# PiezoPreamp.net
KiCad netlist of a schematic drawn in EAGLE
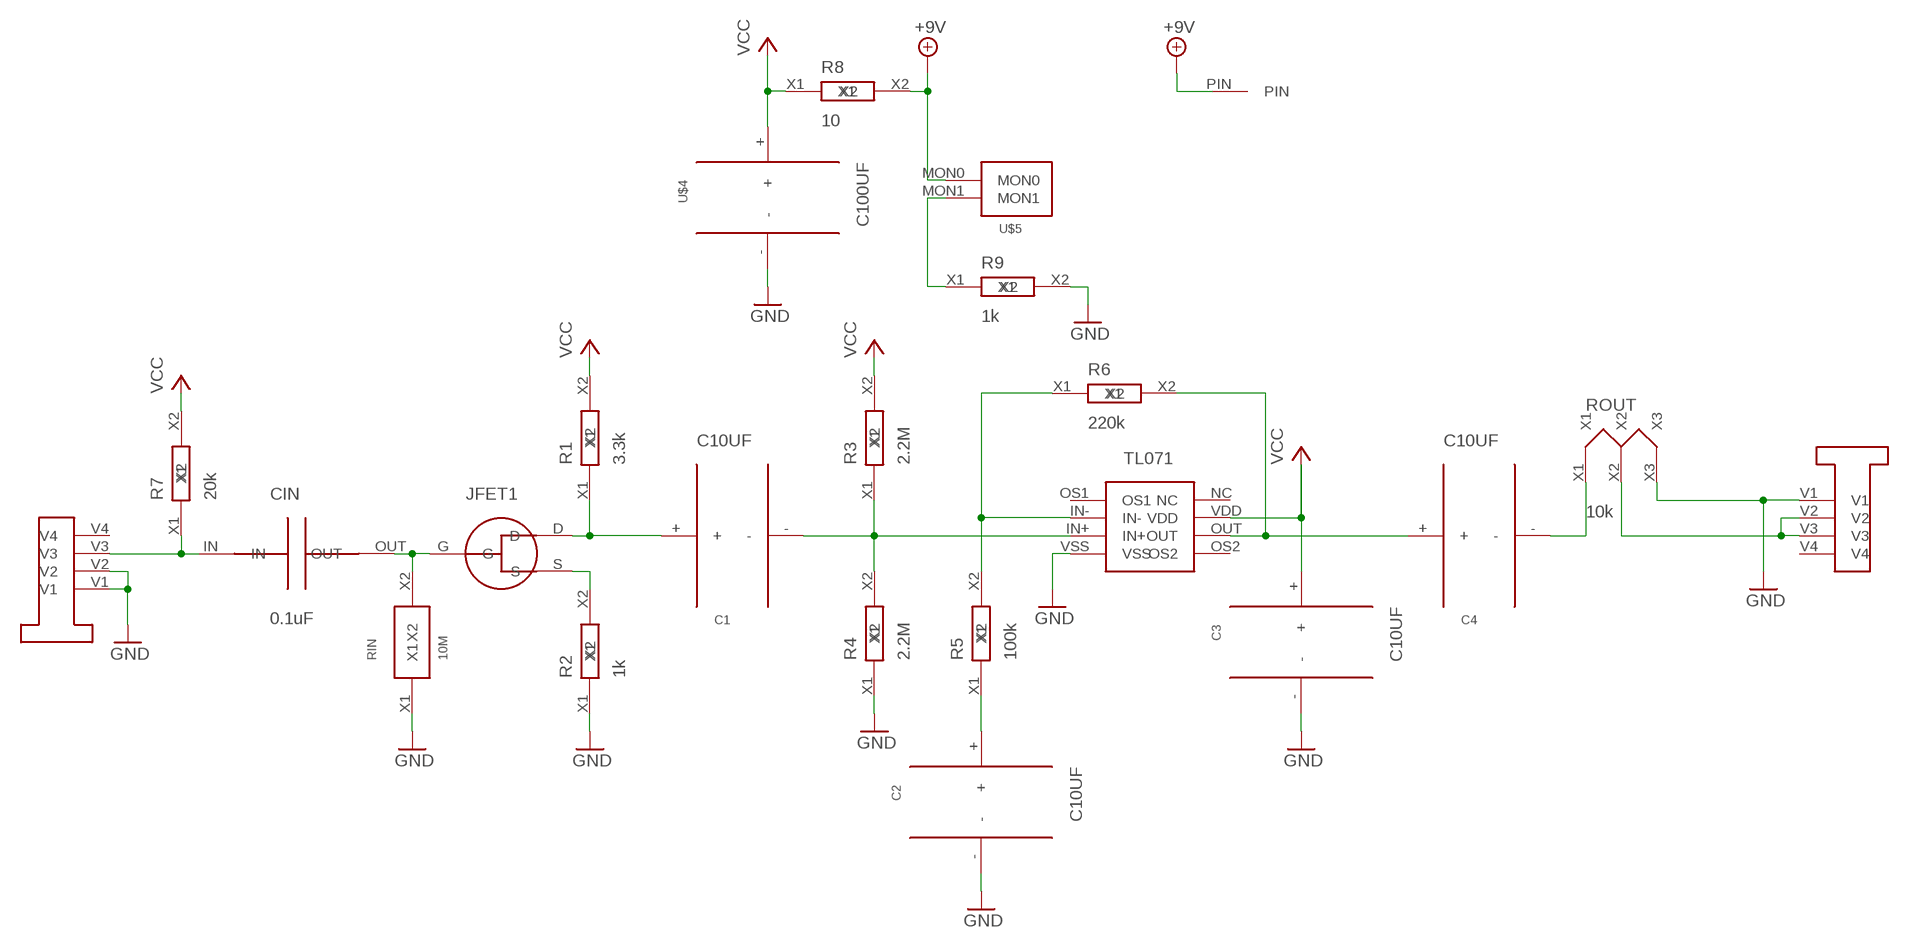
[diagram p0: schematic, sheet 1]

(export (version "E")
  (design (tool "Eeschema 10.0.6"))
  (components
    (comp (ref "C1")
      (value "C10UF")
      (footprint "eagle-import:C10UF")
      (libsource (lib "eagle-import") (part "C10UF"))
    )
    (comp (ref "C2")
      (value "C10UF")
      (footprint "eagle-import:C10UF")
      (libsource (lib "eagle-import") (part "C10UF"))
    )
    (comp (ref "C3")
      (value "C10UF")
      (footprint "eagle-import:C10UF")
      (libsource (lib "eagle-import") (part "C10UF"))
    )
    (comp (ref "C4")
      (value "C10UF")
      (footprint "eagle-import:C10UF")
      (libsource (lib "eagle-import") (part "C10UF"))
    )
    (comp (ref "CIN")
      (value "0.1uF")
      (footprint "eagle-import:C_CER_5MM")
      (libsource (lib "eagle-import") (part "C_CER_5MM"))
    )
    (comp (ref "JFET1")
      (value "2N5457_H")
      (footprint "eagle-import:2N5457_H")
      (libsource (lib "eagle-import") (part "2N5457_H"))
    )
    (comp (ref "R1")
      (value "3.3k")
      (footprint "eagle-import:SMD_2.1X1.25")
      (libsource (lib "eagle-import") (part "R_SMD_2.1X1.25"))
    )
    (comp (ref "R2")
      (value "1k")
      (footprint "eagle-import:SMD_2.1X1.25")
      (libsource (lib "eagle-import") (part "R_SMD_2.1X1.25"))
    )
    (comp (ref "R3")
      (value "2.2M")
      (footprint "eagle-import:SMD_2.1X1.25")
      (libsource (lib "eagle-import") (part "R_SMD_2.1X1.25"))
    )
    (comp (ref "R4")
      (value "2.2M")
      (footprint "eagle-import:SMD_2.1X1.25")
      (libsource (lib "eagle-import") (part "R_SMD_2.1X1.25"))
    )
    (comp (ref "R5")
      (value "100k")
      (footprint "eagle-import:SMD_2.1X1.25")
      (libsource (lib "eagle-import") (part "R_SMD_2.1X1.25"))
    )
    (comp (ref "R6")
      (value "220k")
      (footprint "eagle-import:SMD_2.1X1.25")
      (libsource (lib "eagle-import") (part "R_SMD_2.1X1.25"))
    )
    (comp (ref "R7")
      (value "20k")
      (footprint "eagle-import:SMD_2.1X1.25")
      (libsource (lib "eagle-import") (part "R_SMD_2.1X1.25"))
    )
    (comp (ref "R8")
      (value "10")
      (footprint "eagle-import:SMD_2.1X1.25")
      (libsource (lib "eagle-import") (part "R_SMD_2.1X1.25"))
    )
    (comp (ref "R9")
      (value "1k")
      (footprint "eagle-import:SMD_2.1X1.25")
      (libsource (lib "eagle-import") (part "R_SMD_2.1X1.25"))
    )
    (comp (ref "RIN")
      (value "10M")
      (footprint "eagle-import:R_MOM")
      (libsource (lib "eagle-import") (part "R_MOM"))
    )
    (comp (ref "ROUT")
      (value "10k")
      (footprint "eagle-import:R_VAR_PTV09A")
      (libsource (lib "eagle-import") (part "R_VAR_PTV09A"))
    )
    (comp (ref "TL071")
      (value "TL071")
      (footprint "eagle-import:TL071")
      (libsource (lib "eagle-import") (part "TL071"))
    )
    (comp (ref "U$1")
      (value "ST_AUDIO")
      (footprint "eagle-import:ST_AUDIO")
      (libsource (lib "eagle-import") (part "ST_AUDIO"))
    )
    (comp (ref "U$2")
      (value "ST_AUDIO")
      (footprint "eagle-import:ST_AUDIO")
      (libsource (lib "eagle-import") (part "ST_AUDIO"))
    )
    (comp (ref "U$3")
      (value "PIN_1")
      (footprint "eagle-import:PIN_1")
      (libsource (lib "eagle-import") (part "PIN_1"))
    )
    (comp (ref "U$4")
      (value "C100UF")
      (footprint "eagle-import:C100UF")
      (libsource (lib "eagle-import") (part "C100UF"))
    )
    (comp (ref "U$5")
      (value "MON2PIN")
      (footprint "eagle-import:MON2PIN")
      (libsource (lib "eagle-import") (part "MON2PIN"))
    )
  )
  (nets
    (net (code "1") (name "+9V") (class "Default")
      (node (ref "R8") (pin "X2") (pinfunction "X2_X2") (pintype "bidirectional"))
      (node (ref "U$3") (pin "PIN") (pinfunction "PIN_PIN") (pintype "bidirectional"))
      (node (ref "U$5") (pin "MON0") (pinfunction "MON0_MON0") (pintype "bidirectional"))
    )
    (net (code "2") (name "GND") (class "Default")
      (node (ref "C2") (pin "-") (pinfunction "-_-") (pintype "bidirectional"))
      (node (ref "C3") (pin "-") (pinfunction "-_-") (pintype "bidirectional"))
      (node (ref "R2") (pin "X1") (pinfunction "X1_X1") (pintype "bidirectional"))
      (node (ref "R4") (pin "X1") (pinfunction "X1_X1") (pintype "bidirectional"))
      (node (ref "R9") (pin "X2") (pinfunction "X2_X2") (pintype "bidirectional"))
      (node (ref "RIN") (pin "X1") (pinfunction "X1_X1") (pintype "bidirectional"))
      (node (ref "ROUT") (pin "X3") (pinfunction "X3_X3") (pintype "bidirectional"))
      (node (ref "TL071") (pin "VSS") (pinfunction "VSS_VSS") (pintype "bidirectional"))
      (node (ref "U$1") (pin "V1") (pinfunction "V1_V1") (pintype "bidirectional"))
      (node (ref "U$1") (pin "V2") (pinfunction "V2_V2") (pintype "bidirectional"))
      (node (ref "U$2") (pin "V1") (pinfunction "V1_V1") (pintype "bidirectional"))
      (node (ref "U$4") (pin "-") (pinfunction "-_-") (pintype "bidirectional"))
    )
    (net (code "3") (name "Net-(C1-Pad+)") (class "Default")
      (node (ref "C1") (pin "+") (pinfunction "+_+") (pintype "bidirectional"))
      (node (ref "JFET1") (pin "D") (pinfunction "D_D") (pintype "bidirectional"))
      (node (ref "R1") (pin "X1") (pinfunction "X1_X1") (pintype "bidirectional"))
    )
    (net (code "4") (name "Net-(C1-Pad-)") (class "Default")
      (node (ref "C1") (pin "-") (pinfunction "-_-") (pintype "bidirectional"))
      (node (ref "R3") (pin "X1") (pinfunction "X1_X1") (pintype "bidirectional"))
      (node (ref "R4") (pin "X2") (pinfunction "X2_X2") (pintype "bidirectional"))
      (node (ref "TL071") (pin "IN+") (pinfunction "IN+_IN+") (pintype "bidirectional"))
    )
    (net (code "5") (name "Net-(C2-Pad+)") (class "Default")
      (node (ref "C2") (pin "+") (pinfunction "+_+") (pintype "bidirectional"))
      (node (ref "R5") (pin "X1") (pinfunction "X1_X1") (pintype "bidirectional"))
    )
    (net (code "6") (name "Net-(C4-Pad+)") (class "Default")
      (node (ref "C4") (pin "+") (pinfunction "+_+") (pintype "bidirectional"))
      (node (ref "R6") (pin "X2") (pinfunction "X2_X2") (pintype "bidirectional"))
      (node (ref "TL071") (pin "OUT") (pinfunction "OUT_OUT") (pintype "bidirectional"))
    )
    (net (code "7") (name "Net-(C4-Pad-)") (class "Default")
      (node (ref "C4") (pin "-") (pinfunction "-_-") (pintype "bidirectional"))
      (node (ref "ROUT") (pin "X1") (pinfunction "X1_X1") (pintype "bidirectional"))
    )
    (net (code "8") (name "Net-(CIN-PadIN)") (class "Default")
      (node (ref "CIN") (pin "IN") (pinfunction "IN_IN") (pintype "bidirectional"))
      (node (ref "R7") (pin "X1") (pinfunction "X1_X1") (pintype "bidirectional"))
      (node (ref "U$1") (pin "V3") (pinfunction "V3_V3") (pintype "bidirectional"))
    )
    (net (code "9") (name "Net-(CIN-PadOUT)") (class "Default")
      (node (ref "CIN") (pin "OUT") (pinfunction "OUT_OUT") (pintype "bidirectional"))
      (node (ref "JFET1") (pin "G") (pinfunction "G_G") (pintype "bidirectional"))
      (node (ref "RIN") (pin "X2") (pinfunction "X2_X2") (pintype "bidirectional"))
    )
    (net (code "10") (name "Net-(JFET1-PadS)") (class "Default")
      (node (ref "JFET1") (pin "S") (pinfunction "S_S") (pintype "bidirectional"))
      (node (ref "R2") (pin "X2") (pinfunction "X2_X2") (pintype "bidirectional"))
    )
    (net (code "11") (name "Net-(R5-PadX2)") (class "Default")
      (node (ref "R5") (pin "X2") (pinfunction "X2_X2") (pintype "bidirectional"))
      (node (ref "R6") (pin "X1") (pinfunction "X1_X1") (pintype "bidirectional"))
      (node (ref "TL071") (pin "IN-") (pinfunction "IN-_IN-") (pintype "bidirectional"))
    )
    (net (code "12") (name "Net-(R9-PadX1)") (class "Default")
      (node (ref "R9") (pin "X1") (pinfunction "X1_X1") (pintype "bidirectional"))
      (node (ref "U$5") (pin "MON1") (pinfunction "MON1_MON1") (pintype "bidirectional"))
    )
    (net (code "13") (name "Net-(ROUT-PadX2)") (class "Default")
      (node (ref "ROUT") (pin "X2") (pinfunction "X2_X2") (pintype "bidirectional"))
      (node (ref "U$2") (pin "V2") (pinfunction "V2_V2") (pintype "bidirectional"))
      (node (ref "U$2") (pin "V3") (pinfunction "V3_V3") (pintype "bidirectional"))
    )
    (net (code "14") (name "VCC") (class "Default")
      (node (ref "C3") (pin "+") (pinfunction "+_+") (pintype "bidirectional"))
      (node (ref "R1") (pin "X2") (pinfunction "X2_X2") (pintype "bidirectional"))
      (node (ref "R3") (pin "X2") (pinfunction "X2_X2") (pintype "bidirectional"))
      (node (ref "R7") (pin "X2") (pinfunction "X2_X2") (pintype "bidirectional"))
      (node (ref "R8") (pin "X1") (pinfunction "X1_X1") (pintype "bidirectional"))
      (node (ref "TL071") (pin "VDD") (pinfunction "VDD_VDD") (pintype "bidirectional"))
      (node (ref "U$4") (pin "+") (pinfunction "+_+") (pintype "bidirectional"))
    )
    (net (code "15") (name "unconnected-(TL071-PadNC)") (class "Default")
      (node (ref "TL071") (pin "NC") (pinfunction "NC_NC") (pintype "bidirectional"))
    )
    (net (code "16") (name "unconnected-(TL071-PadOS1)") (class "Default")
      (node (ref "TL071") (pin "OS1") (pinfunction "OS1_OS1") (pintype "bidirectional"))
    )
    (net (code "17") (name "unconnected-(TL071-PadOS2)") (class "Default")
      (node (ref "TL071") (pin "OS2") (pinfunction "OS2_OS2") (pintype "bidirectional"))
    )
    (net (code "18") (name "unconnected-(U$1-PadV4)") (class "Default")
      (node (ref "U$1") (pin "V4") (pinfunction "V4_V4") (pintype "bidirectional"))
    )
    (net (code "19") (name "unconnected-(U$2-PadV4)") (class "Default")
      (node (ref "U$2") (pin "V4") (pinfunction "V4_V4") (pintype "bidirectional"))
    )
  )
)
